# SPECCY2007.net
KiCad netlist of a schematic drawn in Altium Designer
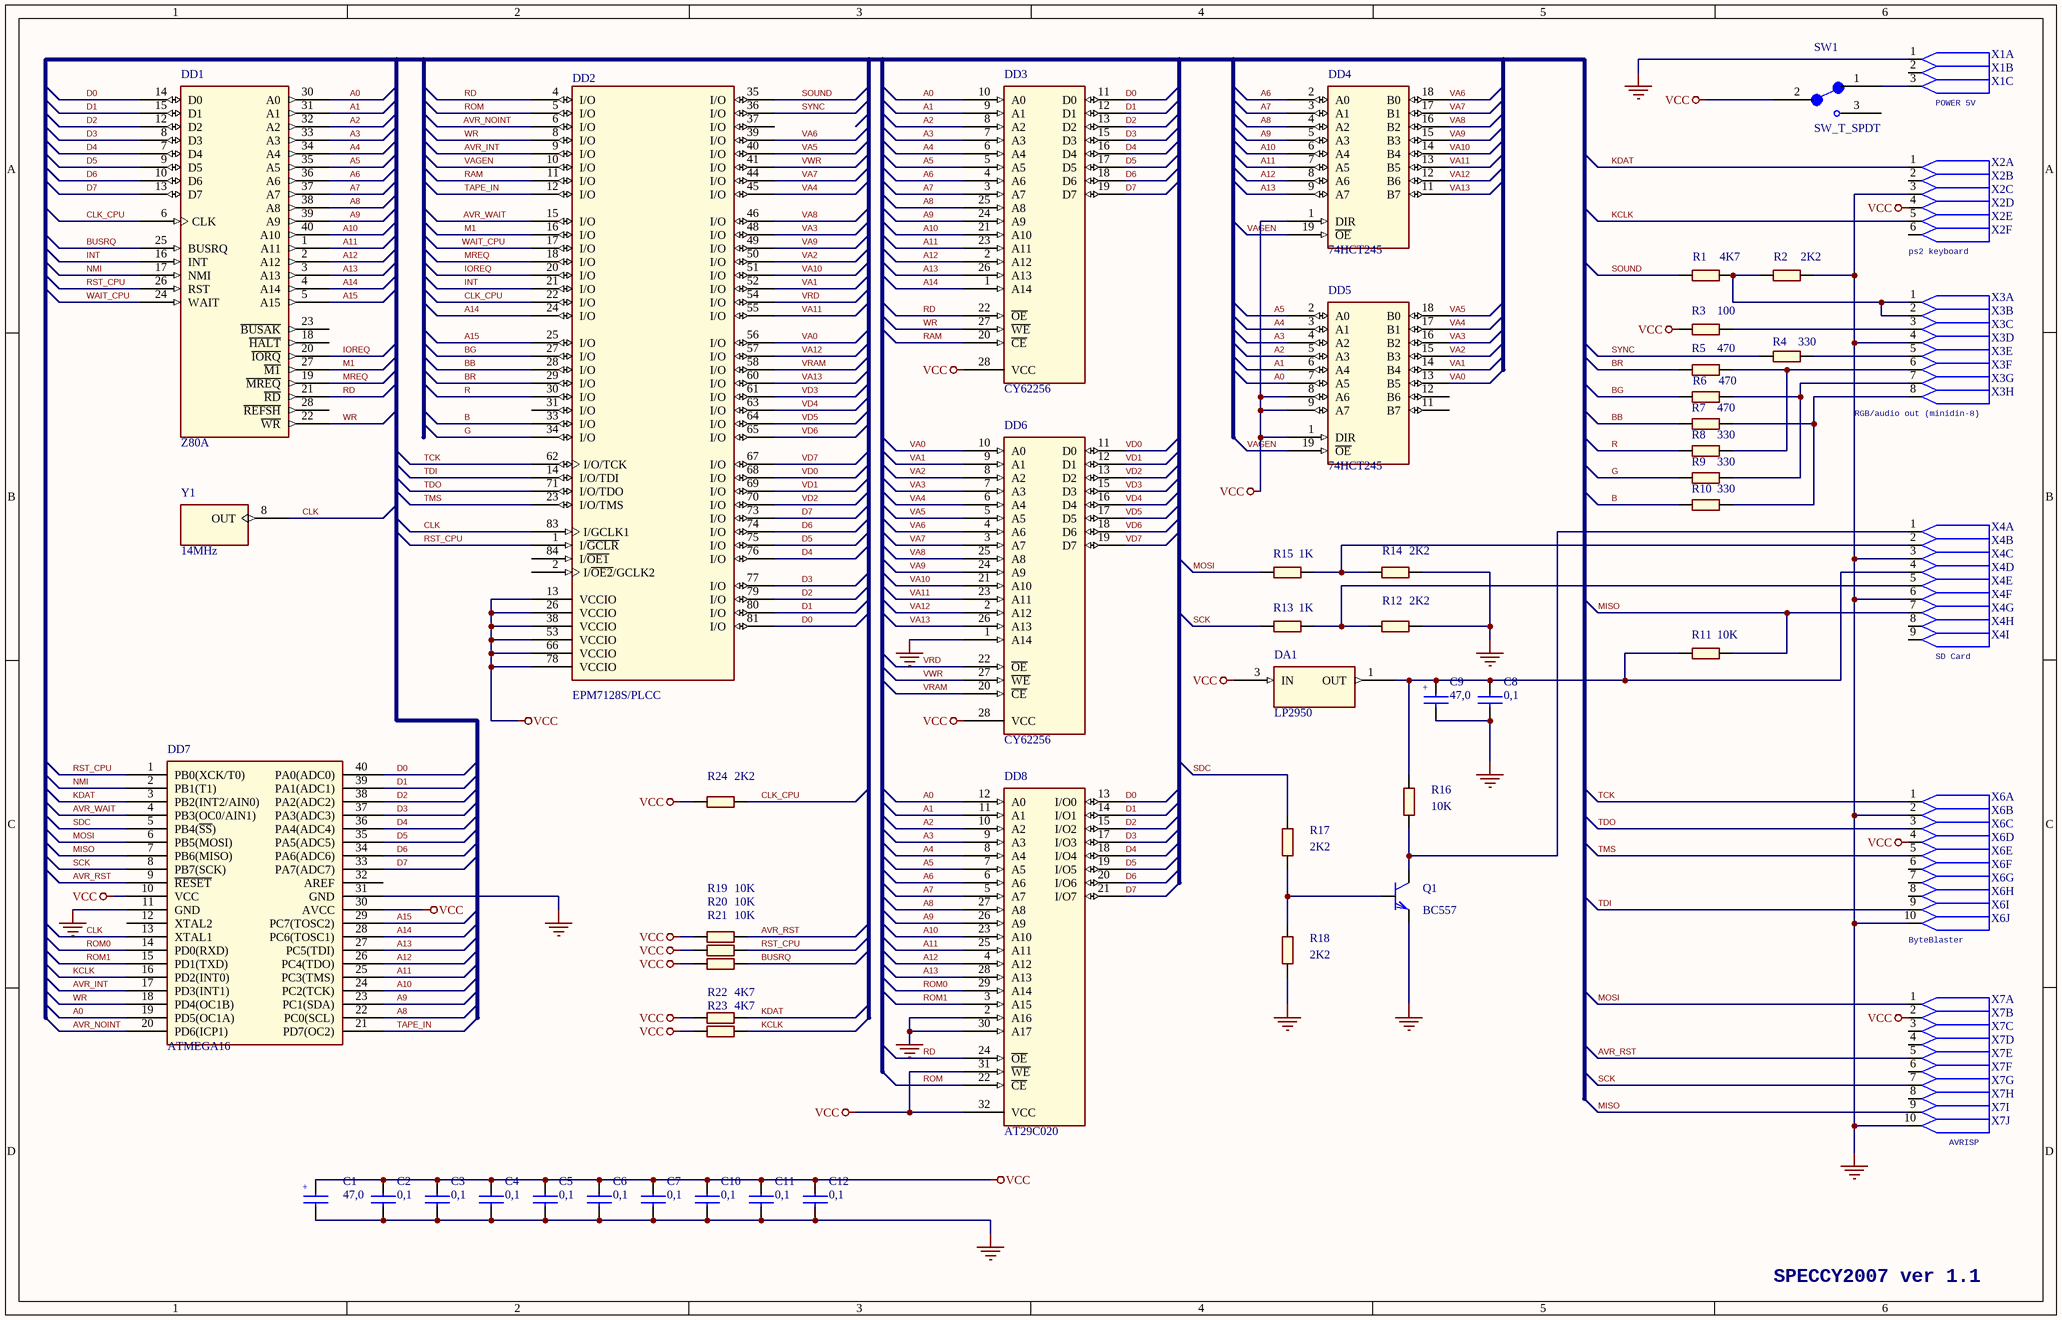
[diagram p0: SPECCY2007.SchDoc]

(export (version "E")
  (design (tool "Eeschema 10.0.6"))
  (components
    (comp (ref "C1")
      (value "47,0")
      (footprint "CAPPOL_2.54")
      (libsource (lib "SPECCY2007_Library") (part "C POL"))
    )
    (comp (ref "C2")
      (value "0,1")
      (footprint "CAP_5.08-7.8x3.2")
      (libsource (lib "SPECCY2007_Library") (part "C"))
    )
    (comp (ref "C3")
      (value "0,1")
      (footprint "CAP_5.08-7.8x3.2")
      (libsource (lib "SPECCY2007_Library") (part "C"))
    )
    (comp (ref "C4")
      (value "0,1")
      (footprint "CAP_5.08-7.8x3.2")
      (libsource (lib "SPECCY2007_Library") (part "C"))
    )
    (comp (ref "C5")
      (value "0,1")
      (footprint "CAP_5.08-7.8x3.2")
      (libsource (lib "SPECCY2007_Library") (part "C"))
    )
    (comp (ref "C6")
      (value "0,1")
      (footprint "CAP_5.08-7.8x3.2")
      (libsource (lib "SPECCY2007_Library") (part "C"))
    )
    (comp (ref "C7")
      (value "0,1")
      (footprint "CAP_5.08-7.8x3.2")
      (libsource (lib "SPECCY2007_Library") (part "C"))
    )
    (comp (ref "C8")
      (value "0,1")
      (footprint "CAP_5.08-7.8x3.2")
      (libsource (lib "SPECCY2007_Library") (part "C"))
    )
    (comp (ref "C9")
      (value "47,0")
      (footprint "CAPPOL_2.54")
      (libsource (lib "SPECCY2007_Library") (part "C POL"))
    )
    (comp (ref "C10")
      (value "0,1")
      (footprint "CAP_5.08-7.8x3.2")
      (libsource (lib "SPECCY2007_Library") (part "C"))
    )
    (comp (ref "C11")
      (value "0,1")
      (footprint "CAP_5.08-7.8x3.2")
      (libsource (lib "SPECCY2007_Library") (part "C"))
    )
    (comp (ref "C12")
      (value "0,1")
      (footprint "CAP_5.08-7.8x3.2")
      (libsource (lib "SPECCY2007_Library") (part "C"))
    )
    (comp (ref "DA1")
      (value "LP2950")
      (footprint "TO92")
      (libsource (lib "SPECCY2007_Library") (part "LP2950"))
    )
    (comp (ref "DD1")
      (value "Z80A")
      (footprint "DIP-40")
      (libsource (lib "SPECCY2007_Library") (part "Z80A"))
    )
    (comp (ref "DD2")
      (value "EPM7128S/PLCC")
      (footprint "PLCC84-Socket+AlteraMAX700S")
      (libsource (lib "SPECCY2007_Library") (part "EPM7128S/PLCC"))
    )
    (comp (ref "DD3")
      (value "CY62256")
      (footprint "DIP-28W")
      (libsource (lib "SPECCY2007_Library") (part "CY62256"))
    )
    (comp (ref "DD4")
      (value "74HCT245")
      (footprint "DIP-20")
      (libsource (lib "SPECCY2007_Library") (part "74HCT245"))
    )
    (comp (ref "DD5")
      (value "74HCT245")
      (footprint "DIP-20")
      (libsource (lib "SPECCY2007_Library") (part "74HCT245"))
    )
    (comp (ref "DD6")
      (value "CY62256")
      (footprint "DIP-28W")
      (libsource (lib "SPECCY2007_Library") (part "CY62256"))
    )
    (comp (ref "DD7")
      (value "ATMEGA16")
      (footprint "DIP-40")
      (libsource (lib "SPECCY2007_Library") (part "ATMEGA16"))
    )
    (comp (ref "DD8")
      (value "AT29C020")
      (footprint "DIP-32/D41.2")
      (libsource (lib "SPECCY2007_Library") (part "AT29C020"))
    )
    (comp (ref "Q1")
      (value "BC557")
      (footprint "TO92")
      (libsource (lib "SPECCY2007_Library") (part "TRANS NPN"))
    )
    (comp (ref "R1") (value "4K7") (footprint "RES_10.16") (libsource (lib "SPECCY2007_Library") (part "R")))
    (comp (ref "R2") (value "2K2") (footprint "RES_10.16") (libsource (lib "SPECCY2007_Library") (part "R")))
    (comp (ref "R3") (value "100") (footprint "RES_10.16") (libsource (lib "SPECCY2007_Library") (part "R")))
    (comp (ref "R4") (value "330") (footprint "RES_10.16") (libsource (lib "SPECCY2007_Library") (part "R")))
    (comp (ref "R5") (value "470") (footprint "RES_10.16") (libsource (lib "SPECCY2007_Library") (part "R")))
    (comp (ref "R6") (value "470") (footprint "RES_10.16") (libsource (lib "SPECCY2007_Library") (part "R")))
    (comp (ref "R7") (value "470") (footprint "RES_10.16") (libsource (lib "SPECCY2007_Library") (part "R")))
    (comp (ref "R8") (value "330") (footprint "RES_10.16") (libsource (lib "SPECCY2007_Library") (part "R")))
    (comp (ref "R9") (value "330") (footprint "RES_10.16") (libsource (lib "SPECCY2007_Library") (part "R")))
    (comp (ref "R10") (value "330") (footprint "RES_10.16") (libsource (lib "SPECCY2007_Library") (part "R")))
    (comp (ref "R11") (value "10K") (footprint "RES_10.16") (libsource (lib "SPECCY2007_Library") (part "R")))
    (comp (ref "R12") (value "2K2") (footprint "RES_10.16") (libsource (lib "SPECCY2007_Library") (part "R")))
    (comp (ref "R13") (value "1K") (footprint "RES_10.16") (libsource (lib "SPECCY2007_Library") (part "R")))
    (comp (ref "R14") (value "2K2") (footprint "RES_10.16") (libsource (lib "SPECCY2007_Library") (part "R")))
    (comp (ref "R15") (value "1K") (footprint "RES_10.16") (libsource (lib "SPECCY2007_Library") (part "R")))
    (comp (ref "R16") (value "10K") (footprint "RES_10.16") (libsource (lib "") (part "R_1")))
    (comp (ref "R17") (value "2K2") (footprint "RES_10.16") (libsource (lib "") (part "R_1")))
    (comp (ref "R18") (value "2K2") (footprint "RES_10.16") (libsource (lib "") (part "R_1")))
    (comp (ref "R19") (value "10K") (footprint "RES_10.16") (libsource (lib "SPECCY2007_Library") (part "R")))
    (comp (ref "R20") (value "10K") (footprint "RES_10.16") (libsource (lib "SPECCY2007_Library") (part "R")))
    (comp (ref "R21") (value "10K") (footprint "RES_10.16") (libsource (lib "SPECCY2007_Library") (part "R")))
    (comp (ref "R22") (value "4K7") (footprint "RES_10.16") (libsource (lib "SPECCY2007_Library") (part "R")))
    (comp (ref "R23") (value "4K7") (footprint "RES_10.16") (libsource (lib "SPECCY2007_Library") (part "R")))
    (comp (ref "R24") (value "2K2") (footprint "RES_10.16") (libsource (lib "SPECCY2007_Library") (part "R")))
    (comp (ref "SW1")
      (value "SW_T_SPDT")
      (footprint "SW_T_SPDT")
      (libsource (lib "SPECCY2007_Library") (part "SW_T_SPDT"))
    )
    (comp (ref "X1")
      (value "X3")
      (footprint "CONN JACK PWR")
      (libsource (lib "SPECCY2007_Library") (part "X3"))
    )
    (comp (ref "X2") (value "X6") (footprint "Mini-DIN6") (libsource (lib "SPECCY2007_Library") (part "X6")))
    (comp (ref "X3") (value "X8") (footprint "Mini-DIN8") (libsource (lib "SPECCY2007_Library") (part "X8")))
    (comp (ref "X4")
      (value "X9")
      (footprint "SD Card socket")
      (description "SD Card socket")
      (libsource (lib "SPECCY2007_Library") (part "X9"))
    )
    (comp (ref "X6")
      (value "X10")
      (footprint "Double row pin strip 5 way")
      (libsource (lib "SPECCY2007_Library") (part "X10"))
    )
    (comp (ref "X7")
      (value "X10")
      (footprint "Double row pin strip 5 way")
      (libsource (lib "SPECCY2007_Library") (part "X10"))
    )
    (comp (ref "Y1")
      (value "14MHz")
      (footprint "OSC14")
      (libsource (lib "SPECCY2007_Library") (part "OSC14"))
    )
  )
  (nets
    (net (code "1") (name "/A0") (class "Default")
      (node (ref "DD1") (pin "30") (pinfunction "A0_30") (pintype "output"))
      (node (ref "DD3") (pin "10") (pinfunction "A0_10") (pintype "input"))
      (node (ref "DD5") (pin "7") (pinfunction "A5_7") (pintype "bidirectional"))
      (node (ref "DD7") (pin "19") (pinfunction "PD5(OC1A)_19") (pintype "passive"))
      (node (ref "DD8") (pin "12") (pinfunction "A0_12") (pintype "input"))
    )
    (net (code "2") (name "/A1") (class "Default")
      (node (ref "DD1") (pin "31") (pinfunction "A1_31") (pintype "output"))
      (node (ref "DD3") (pin "9") (pinfunction "A1_9") (pintype "input"))
      (node (ref "DD5") (pin "6") (pinfunction "A4_6") (pintype "bidirectional"))
      (node (ref "DD8") (pin "11") (pinfunction "A1_11") (pintype "input"))
    )
    (net (code "3") (name "/A2") (class "Default")
      (node (ref "DD1") (pin "32") (pinfunction "A2_32") (pintype "output"))
      (node (ref "DD3") (pin "8") (pinfunction "A2_8") (pintype "input"))
      (node (ref "DD5") (pin "5") (pinfunction "A3_5") (pintype "bidirectional"))
      (node (ref "DD8") (pin "10") (pinfunction "A2_10") (pintype "input"))
    )
    (net (code "4") (name "/A3") (class "Default")
      (node (ref "DD1") (pin "33") (pinfunction "A3_33") (pintype "output"))
      (node (ref "DD3") (pin "7") (pinfunction "A3_7") (pintype "input"))
      (node (ref "DD5") (pin "4") (pinfunction "A2_4") (pintype "bidirectional"))
      (node (ref "DD8") (pin "9") (pinfunction "A3_9") (pintype "input"))
    )
    (net (code "5") (name "/A4") (class "Default")
      (node (ref "DD1") (pin "34") (pinfunction "A4_34") (pintype "output"))
      (node (ref "DD3") (pin "6") (pinfunction "A4_6") (pintype "input"))
      (node (ref "DD5") (pin "3") (pinfunction "A1_3") (pintype "bidirectional"))
      (node (ref "DD8") (pin "8") (pinfunction "A4_8") (pintype "input"))
    )
    (net (code "6") (name "/A5") (class "Default")
      (node (ref "DD1") (pin "35") (pinfunction "A5_35") (pintype "output"))
      (node (ref "DD3") (pin "5") (pinfunction "A5_5") (pintype "input"))
      (node (ref "DD5") (pin "2") (pinfunction "A0_2") (pintype "bidirectional"))
      (node (ref "DD8") (pin "7") (pinfunction "A5_7") (pintype "input"))
    )
    (net (code "7") (name "/A6") (class "Default")
      (node (ref "DD1") (pin "36") (pinfunction "A6_36") (pintype "output"))
      (node (ref "DD3") (pin "4") (pinfunction "A6_4") (pintype "input"))
      (node (ref "DD4") (pin "2") (pinfunction "A0_2") (pintype "bidirectional"))
      (node (ref "DD8") (pin "6") (pinfunction "A6_6") (pintype "input"))
    )
    (net (code "8") (name "/A7") (class "Default")
      (node (ref "DD1") (pin "37") (pinfunction "A7_37") (pintype "output"))
      (node (ref "DD3") (pin "3") (pinfunction "A7_3") (pintype "input"))
      (node (ref "DD4") (pin "3") (pinfunction "A1_3") (pintype "bidirectional"))
      (node (ref "DD8") (pin "5") (pinfunction "A7_5") (pintype "input"))
    )
    (net (code "9") (name "/A8") (class "Default")
      (node (ref "DD1") (pin "38") (pinfunction "A8_38") (pintype "output"))
      (node (ref "DD3") (pin "25") (pinfunction "A8_25") (pintype "input"))
      (node (ref "DD4") (pin "4") (pinfunction "A2_4") (pintype "bidirectional"))
      (node (ref "DD7") (pin "22") (pinfunction "PC0(SCL)_22") (pintype "passive"))
      (node (ref "DD8") (pin "27") (pinfunction "A8_27") (pintype "input"))
    )
    (net (code "10") (name "/A9") (class "Default")
      (node (ref "DD1") (pin "39") (pinfunction "A9_39") (pintype "output"))
      (node (ref "DD3") (pin "24") (pinfunction "A9_24") (pintype "input"))
      (node (ref "DD4") (pin "5") (pinfunction "A3_5") (pintype "bidirectional"))
      (node (ref "DD7") (pin "23") (pinfunction "PC1(SDA)_23") (pintype "passive"))
      (node (ref "DD8") (pin "26") (pinfunction "A9_26") (pintype "input"))
    )
    (net (code "11") (name "/A10") (class "Default")
      (node (ref "DD1") (pin "40") (pinfunction "A10_40") (pintype "output"))
      (node (ref "DD3") (pin "21") (pinfunction "A10_21") (pintype "input"))
      (node (ref "DD4") (pin "6") (pinfunction "A4_6") (pintype "bidirectional"))
      (node (ref "DD7") (pin "24") (pinfunction "PC2(TCK)_24") (pintype "passive"))
      (node (ref "DD8") (pin "23") (pinfunction "A10_23") (pintype "input"))
    )
    (net (code "12") (name "/A11") (class "Default")
      (node (ref "DD1") (pin "1") (pinfunction "A11_1") (pintype "output"))
      (node (ref "DD3") (pin "23") (pinfunction "A11_23") (pintype "input"))
      (node (ref "DD4") (pin "7") (pinfunction "A5_7") (pintype "bidirectional"))
      (node (ref "DD7") (pin "25") (pinfunction "PC3(TMS)_25") (pintype "passive"))
      (node (ref "DD8") (pin "25") (pinfunction "A11_25") (pintype "input"))
    )
    (net (code "13") (name "/A12") (class "Default")
      (node (ref "DD1") (pin "2") (pinfunction "A12_2") (pintype "output"))
      (node (ref "DD3") (pin "2") (pinfunction "A12_2") (pintype "input"))
      (node (ref "DD4") (pin "8") (pinfunction "A6_8") (pintype "bidirectional"))
      (node (ref "DD7") (pin "26") (pinfunction "PC4(TDO)_26") (pintype "passive"))
      (node (ref "DD8") (pin "4") (pinfunction "A12_4") (pintype "input"))
    )
    (net (code "14") (name "/A13") (class "Default")
      (node (ref "DD1") (pin "3") (pinfunction "A13_3") (pintype "output"))
      (node (ref "DD3") (pin "26") (pinfunction "A13_26") (pintype "input"))
      (node (ref "DD4") (pin "9") (pinfunction "A7_9") (pintype "bidirectional"))
      (node (ref "DD7") (pin "27") (pinfunction "PC5(TDI)_27") (pintype "passive"))
      (node (ref "DD8") (pin "28") (pinfunction "A13_28") (pintype "input"))
    )
    (net (code "15") (name "/A14") (class "Default")
      (node (ref "DD1") (pin "4") (pinfunction "A14_4") (pintype "output"))
      (node (ref "DD2") (pin "24") (pinfunction "I/O_24") (pintype "bidirectional"))
      (node (ref "DD3") (pin "1") (pinfunction "A14_1") (pintype "input"))
      (node (ref "DD7") (pin "28") (pinfunction "PC6(TOSC1)_28") (pintype "passive"))
    )
    (net (code "16") (name "/A15") (class "Default")
      (node (ref "DD1") (pin "5") (pinfunction "A15_5") (pintype "output"))
      (node (ref "DD2") (pin "25") (pinfunction "I/O_25") (pintype "bidirectional"))
      (node (ref "DD7") (pin "29") (pinfunction "PC7(TOSC2)_29") (pintype "passive"))
    )
    (net (code "17") (name "/AVR_INT") (class "Default")
      (node (ref "DD2") (pin "9") (pinfunction "I/O_9") (pintype "bidirectional"))
      (node (ref "DD7") (pin "17") (pinfunction "PD3(INT1)_17") (pintype "passive"))
    )
    (net (code "18") (name "/AVR_NOINT") (class "Default")
      (node (ref "DD2") (pin "6") (pinfunction "I/O_6") (pintype "bidirectional"))
      (node (ref "DD7") (pin "20") (pinfunction "PD6(ICP1)_20") (pintype "passive"))
    )
    (net (code "19") (name "/AVR_RST") (class "Default")
      (node (ref "DD7") (pin "9") (pinfunction "~{RESET}_9") (pintype "passive"))
      (node (ref "R19") (pin "2") (pinfunction "2_2") (pintype "passive"))
      (node (ref "X7") (pin "5") (pinfunction "CON_5") (pintype "passive"))
    )
    (net (code "20") (name "/AVR_WAIT") (class "Default")
      (node (ref "DD2") (pin "15") (pinfunction "I/O_15") (pintype "bidirectional"))
      (node (ref "DD7") (pin "4") (pinfunction "PB3(OC0/AIN1)_4") (pintype "passive"))
    )
    (net (code "21") (name "/B") (class "Default")
      (node (ref "DD2") (pin "33") (pinfunction "I/O_33") (pintype "bidirectional"))
      (node (ref "R10") (pin "1") (pinfunction "1_1") (pintype "passive"))
    )
    (net (code "22") (name "/BB") (class "Default")
      (node (ref "DD2") (pin "28") (pinfunction "I/O_28") (pintype "bidirectional"))
      (node (ref "R7") (pin "1") (pinfunction "1_1") (pintype "passive"))
    )
    (net (code "23") (name "/BG") (class "Default")
      (node (ref "DD2") (pin "27") (pinfunction "I/O_27") (pintype "bidirectional"))
      (node (ref "R6") (pin "1") (pinfunction "1_1") (pintype "passive"))
    )
    (net (code "24") (name "/BR") (class "Default")
      (node (ref "DD2") (pin "29") (pinfunction "I/O_29") (pintype "bidirectional"))
      (node (ref "R5") (pin "1") (pinfunction "1_1") (pintype "passive"))
    )
    (net (code "25") (name "/BUSRQ") (class "Default")
      (node (ref "DD1") (pin "25") (pinfunction "BUSRQ_25") (pintype "input"))
      (node (ref "R21") (pin "2") (pinfunction "2_2") (pintype "passive"))
    )
    (net (code "26") (name "/CLK") (class "Default")
      (node (ref "DD2") (pin "83") (pinfunction "I/GCLK1_83") (pintype "input"))
      (node (ref "DD7") (pin "13") (pinfunction "XTAL1_13") (pintype "passive"))
      (node (ref "Y1") (pin "8") (pinfunction "OUT_8") (pintype "output"))
    )
    (net (code "27") (name "/CLK_CPU") (class "Default")
      (node (ref "DD1") (pin "6") (pinfunction "CLK_6") (pintype "input"))
      (node (ref "DD2") (pin "22") (pinfunction "I/O_22") (pintype "bidirectional"))
      (node (ref "R24") (pin "2") (pinfunction "2_2") (pintype "passive"))
    )
    (net (code "28") (name "/D0") (class "Default")
      (node (ref "DD1") (pin "14") (pinfunction "D0_14") (pintype "bidirectional"))
      (node (ref "DD2") (pin "81") (pinfunction "I/O_81") (pintype "bidirectional"))
      (node (ref "DD3") (pin "11") (pinfunction "D0_11") (pintype "bidirectional"))
      (node (ref "DD7") (pin "40") (pinfunction "PA0(ADC0)_40") (pintype "passive"))
      (node (ref "DD8") (pin "13") (pinfunction "I/O0_13") (pintype "bidirectional"))
    )
    (net (code "29") (name "/D1") (class "Default")
      (node (ref "DD1") (pin "15") (pinfunction "D1_15") (pintype "bidirectional"))
      (node (ref "DD2") (pin "80") (pinfunction "I/O_80") (pintype "bidirectional"))
      (node (ref "DD3") (pin "12") (pinfunction "D1_12") (pintype "bidirectional"))
      (node (ref "DD7") (pin "39") (pinfunction "PA1(ADC1)_39") (pintype "passive"))
      (node (ref "DD8") (pin "14") (pinfunction "I/O1_14") (pintype "bidirectional"))
    )
    (net (code "30") (name "/D2") (class "Default")
      (node (ref "DD1") (pin "12") (pinfunction "D2_12") (pintype "bidirectional"))
      (node (ref "DD2") (pin "79") (pinfunction "I/O_79") (pintype "bidirectional"))
      (node (ref "DD3") (pin "13") (pinfunction "D2_13") (pintype "bidirectional"))
      (node (ref "DD7") (pin "38") (pinfunction "PA2(ADC2)_38") (pintype "passive"))
      (node (ref "DD8") (pin "15") (pinfunction "I/O2_15") (pintype "bidirectional"))
    )
    (net (code "31") (name "/D3") (class "Default")
      (node (ref "DD1") (pin "8") (pinfunction "D3_8") (pintype "bidirectional"))
      (node (ref "DD2") (pin "77") (pinfunction "I/O_77") (pintype "bidirectional"))
      (node (ref "DD3") (pin "15") (pinfunction "D3_15") (pintype "bidirectional"))
      (node (ref "DD7") (pin "37") (pinfunction "PA3(ADC3)_37") (pintype "passive"))
      (node (ref "DD8") (pin "17") (pinfunction "I/O3_17") (pintype "bidirectional"))
    )
    (net (code "32") (name "/D4") (class "Default")
      (node (ref "DD1") (pin "7") (pinfunction "D4_7") (pintype "bidirectional"))
      (node (ref "DD2") (pin "76") (pinfunction "I/O_76") (pintype "bidirectional"))
      (node (ref "DD3") (pin "16") (pinfunction "D4_16") (pintype "bidirectional"))
      (node (ref "DD7") (pin "36") (pinfunction "PA4(ADC4)_36") (pintype "passive"))
      (node (ref "DD8") (pin "18") (pinfunction "I/O4_18") (pintype "bidirectional"))
    )
    (net (code "33") (name "/D5") (class "Default")
      (node (ref "DD1") (pin "9") (pinfunction "D5_9") (pintype "bidirectional"))
      (node (ref "DD2") (pin "75") (pinfunction "I/O_75") (pintype "bidirectional"))
      (node (ref "DD3") (pin "17") (pinfunction "D5_17") (pintype "bidirectional"))
      (node (ref "DD7") (pin "35") (pinfunction "PA5(ADC5)_35") (pintype "passive"))
      (node (ref "DD8") (pin "19") (pinfunction "I/O5_19") (pintype "bidirectional"))
    )
    (net (code "34") (name "/D6") (class "Default")
      (node (ref "DD1") (pin "10") (pinfunction "D6_10") (pintype "bidirectional"))
      (node (ref "DD2") (pin "74") (pinfunction "I/O_74") (pintype "bidirectional"))
      (node (ref "DD3") (pin "18") (pinfunction "D6_18") (pintype "bidirectional"))
      (node (ref "DD7") (pin "34") (pinfunction "PA6(ADC6)_34") (pintype "passive"))
      (node (ref "DD8") (pin "20") (pinfunction "I/O6_20") (pintype "bidirectional"))
    )
    (net (code "35") (name "/D7") (class "Default")
      (node (ref "DD1") (pin "13") (pinfunction "D7_13") (pintype "bidirectional"))
      (node (ref "DD2") (pin "73") (pinfunction "I/O_73") (pintype "bidirectional"))
      (node (ref "DD3") (pin "19") (pinfunction "D7_19") (pintype "bidirectional"))
      (node (ref "DD7") (pin "33") (pinfunction "PA7(ADC7)_33") (pintype "passive"))
      (node (ref "DD8") (pin "21") (pinfunction "I/O7_21") (pintype "bidirectional"))
    )
    (net (code "36") (name "/G") (class "Default")
      (node (ref "DD2") (pin "34") (pinfunction "I/O_34") (pintype "bidirectional"))
      (node (ref "R9") (pin "1") (pinfunction "1_1") (pintype "passive"))
    )
    (net (code "37") (name "/INT") (class "Default")
      (node (ref "DD1") (pin "16") (pinfunction "INT_16") (pintype "input"))
      (node (ref "DD2") (pin "21") (pinfunction "I/O_21") (pintype "bidirectional"))
    )
    (net (code "38") (name "/IOREQ") (class "Default")
      (node (ref "DD1") (pin "20") (pinfunction "~{IORQ}_20") (pintype "output"))
      (node (ref "DD2") (pin "20") (pinfunction "I/O_20") (pintype "bidirectional"))
    )
    (net (code "39") (name "/KCLK") (class "Default")
      (node (ref "DD7") (pin "16") (pinfunction "PD2(INT0)_16") (pintype "passive"))
      (node (ref "R23") (pin "2") (pinfunction "2_2") (pintype "passive"))
      (node (ref "X2") (pin "5") (pinfunction "CON_5") (pintype "passive"))
    )
    (net (code "40") (name "/KDAT") (class "Default")
      (node (ref "DD7") (pin "3") (pinfunction "PB2(INT2/AIN0)_3") (pintype "passive"))
      (node (ref "R22") (pin "2") (pinfunction "2_2") (pintype "passive"))
      (node (ref "X2") (pin "1") (pinfunction "CON_1") (pintype "passive"))
    )
    (net (code "41") (name "/M1") (class "Default")
      (node (ref "DD1") (pin "27") (pinfunction "~{M1}_27") (pintype "output"))
      (node (ref "DD2") (pin "16") (pinfunction "I/O_16") (pintype "bidirectional"))
    )
    (net (code "42") (name "/MISO") (class "Default")
      (node (ref "DD7") (pin "7") (pinfunction "PB6(MISO)_7") (pintype "passive"))
      (node (ref "R11") (pin "2") (pinfunction "2_2") (pintype "passive"))
      (node (ref "X4") (pin "7") (pinfunction "CON_7") (pintype "passive"))
      (node (ref "X7") (pin "9") (pinfunction "CON_9") (pintype "passive"))
    )
    (net (code "43") (name "/MOSI") (class "Default")
      (node (ref "DD7") (pin "6") (pinfunction "PB5(MOSI)_6") (pintype "passive"))
      (node (ref "R15") (pin "1") (pinfunction "1_1") (pintype "passive"))
      (node (ref "X7") (pin "1") (pinfunction "CON_1") (pintype "passive"))
    )
    (net (code "44") (name "/MREQ") (class "Default")
      (node (ref "DD1") (pin "19") (pinfunction "~{MREQ}_19") (pintype "output"))
      (node (ref "DD2") (pin "18") (pinfunction "I/O_18") (pintype "bidirectional"))
    )
    (net (code "45") (name "/NMI") (class "Default")
      (node (ref "DD1") (pin "17") (pinfunction "NMI_17") (pintype "input"))
      (node (ref "DD7") (pin "2") (pinfunction "PB1(T1)_2") (pintype "passive"))
    )
    (net (code "46") (name "/R") (class "Default")
      (node (ref "DD2") (pin "30") (pinfunction "I/O_30") (pintype "bidirectional"))
      (node (ref "R8") (pin "1") (pinfunction "1_1") (pintype "passive"))
    )
    (net (code "47") (name "/RAM") (class "Default")
      (node (ref "DD2") (pin "11") (pinfunction "I/O_11") (pintype "bidirectional"))
      (node (ref "DD3") (pin "20") (pinfunction "~{CE}_20") (pintype "input"))
    )
    (net (code "48") (name "/RD") (class "Default")
      (node (ref "DD1") (pin "21") (pinfunction "~{RD}_21") (pintype "output"))
      (node (ref "DD2") (pin "4") (pinfunction "I/O_4") (pintype "bidirectional"))
      (node (ref "DD3") (pin "22") (pinfunction "~{OE}_22") (pintype "input"))
      (node (ref "DD8") (pin "24") (pinfunction "~{OE}_24") (pintype "input"))
    )
    (net (code "49") (name "/ROM") (class "Default")
      (node (ref "DD2") (pin "5") (pinfunction "I/O_5") (pintype "bidirectional"))
      (node (ref "DD8") (pin "22") (pinfunction "~{CE}_22") (pintype "input"))
    )
    (net (code "50") (name "/ROM0") (class "Default")
      (node (ref "DD7") (pin "14") (pinfunction "PD0(RXD)_14") (pintype "passive"))
      (node (ref "DD8") (pin "29") (pinfunction "A14_29") (pintype "input"))
    )
    (net (code "51") (name "/ROM1") (class "Default")
      (node (ref "DD7") (pin "15") (pinfunction "PD1(TXD)_15") (pintype "passive"))
      (node (ref "DD8") (pin "3") (pinfunction "A15_3") (pintype "input"))
    )
    (net (code "52") (name "/RST_CPU") (class "Default")
      (node (ref "DD1") (pin "26") (pinfunction "RST_26") (pintype "input"))
      (node (ref "DD2") (pin "1") (pinfunction "I/~{GCLR}_1") (pintype "input"))
      (node (ref "DD7") (pin "1") (pinfunction "PB0(XCK/T0)_1") (pintype "passive"))
      (node (ref "R20") (pin "2") (pinfunction "2_2") (pintype "passive"))
    )
    (net (code "53") (name "/SCK") (class "Default")
      (node (ref "DD7") (pin "8") (pinfunction "PB7(SCK)_8") (pintype "passive"))
      (node (ref "R13") (pin "1") (pinfunction "1_1") (pintype "passive"))
      (node (ref "X7") (pin "7") (pinfunction "CON_7") (pintype "passive"))
    )
    (net (code "54") (name "/SDC") (class "Default")
      (node (ref "DD7") (pin "5") (pinfunction "PB4(~{SS})_5") (pintype "passive"))
      (node (ref "R17") (pin "2") (pinfunction "2_2") (pintype "passive"))
    )
    (net (code "55") (name "/SOUND") (class "Default")
      (node (ref "DD2") (pin "35") (pinfunction "I/O_35") (pintype "bidirectional"))
      (node (ref "R1") (pin "1") (pinfunction "1_1") (pintype "passive"))
    )
    (net (code "56") (name "/SYNC") (class "Default")
      (node (ref "DD2") (pin "36") (pinfunction "I/O_36") (pintype "bidirectional"))
      (node (ref "R4") (pin "1") (pinfunction "1_1") (pintype "passive"))
    )
    (net (code "57") (name "/TAPE_IN") (class "Default")
      (node (ref "DD2") (pin "12") (pinfunction "I/O_12") (pintype "bidirectional"))
      (node (ref "DD7") (pin "21") (pinfunction "PD7(OC2)_21") (pintype "passive"))
    )
    (net (code "58") (name "/TCK") (class "Default")
      (node (ref "DD2") (pin "62") (pinfunction "I/O/TCK_62") (pintype "bidirectional"))
      (node (ref "X6") (pin "1") (pinfunction "CON_1") (pintype "passive"))
    )
    (net (code "59") (name "/TDI") (class "Default")
      (node (ref "DD2") (pin "14") (pinfunction "I/O/TDI_14") (pintype "bidirectional"))
      (node (ref "X6") (pin "9") (pinfunction "CON_9") (pintype "passive"))
    )
    (net (code "60") (name "/TDO") (class "Default")
      (node (ref "DD2") (pin "71") (pinfunction "I/O/TDO_71") (pintype "bidirectional"))
      (node (ref "X6") (pin "3") (pinfunction "CON_3") (pintype "passive"))
    )
    (net (code "61") (name "/TMS") (class "Default")
      (node (ref "DD2") (pin "23") (pinfunction "I/O/TMS_23") (pintype "bidirectional"))
      (node (ref "X6") (pin "5") (pinfunction "CON_5") (pintype "passive"))
    )
    (net (code "62") (name "/VA0") (class "Default")
      (node (ref "DD2") (pin "56") (pinfunction "I/O_56") (pintype "bidirectional"))
      (node (ref "DD5") (pin "13") (pinfunction "B5_13") (pintype "bidirectional"))
      (node (ref "DD6") (pin "10") (pinfunction "A0_10") (pintype "input"))
    )
    (net (code "63") (name "/VA1") (class "Default")
      (node (ref "DD2") (pin "52") (pinfunction "I/O_52") (pintype "bidirectional"))
      (node (ref "DD5") (pin "14") (pinfunction "B4_14") (pintype "bidirectional"))
      (node (ref "DD6") (pin "9") (pinfunction "A1_9") (pintype "input"))
    )
    (net (code "64") (name "/VA2") (class "Default")
      (node (ref "DD2") (pin "50") (pinfunction "I/O_50") (pintype "bidirectional"))
      (node (ref "DD5") (pin "15") (pinfunction "B3_15") (pintype "bidirectional"))
      (node (ref "DD6") (pin "8") (pinfunction "A2_8") (pintype "input"))
    )
    (net (code "65") (name "/VA3") (class "Default")
      (node (ref "DD2") (pin "48") (pinfunction "I/O_48") (pintype "bidirectional"))
      (node (ref "DD5") (pin "16") (pinfunction "B2_16") (pintype "bidirectional"))
      (node (ref "DD6") (pin "7") (pinfunction "A3_7") (pintype "input"))
    )
    (net (code "66") (name "/VA4") (class "Default")
      (node (ref "DD2") (pin "45") (pinfunction "I/O_45") (pintype "bidirectional"))
      (node (ref "DD5") (pin "17") (pinfunction "B1_17") (pintype "bidirectional"))
      (node (ref "DD6") (pin "6") (pinfunction "A4_6") (pintype "input"))
    )
    (net (code "67") (name "/VA5") (class "Default")
      (node (ref "DD2") (pin "40") (pinfunction "I/O_40") (pintype "bidirectional"))
      (node (ref "DD5") (pin "18") (pinfunction "B0_18") (pintype "bidirectional"))
      (node (ref "DD6") (pin "5") (pinfunction "A5_5") (pintype "input"))
    )
    (net (code "68") (name "/VA6") (class "Default")
      (node (ref "DD2") (pin "39") (pinfunction "I/O_39") (pintype "bidirectional"))
      (node (ref "DD4") (pin "18") (pinfunction "B0_18") (pintype "bidirectional"))
      (node (ref "DD6") (pin "4") (pinfunction "A6_4") (pintype "input"))
    )
    (net (code "69") (name "/VA7") (class "Default")
      (node (ref "DD2") (pin "44") (pinfunction "I/O_44") (pintype "bidirectional"))
      (node (ref "DD4") (pin "17") (pinfunction "B1_17") (pintype "bidirectional"))
      (node (ref "DD6") (pin "3") (pinfunction "A7_3") (pintype "input"))
    )
    (net (code "70") (name "/VA8") (class "Default")
      (node (ref "DD2") (pin "46") (pinfunction "I/O_46") (pintype "bidirectional"))
      (node (ref "DD4") (pin "16") (pinfunction "B2_16") (pintype "bidirectional"))
      (node (ref "DD6") (pin "25") (pinfunction "A8_25") (pintype "input"))
    )
    (net (code "71") (name "/VA9") (class "Default")
      (node (ref "DD2") (pin "49") (pinfunction "I/O_49") (pintype "bidirectional"))
      (node (ref "DD4") (pin "15") (pinfunction "B3_15") (pintype "bidirectional"))
      (node (ref "DD6") (pin "24") (pinfunction "A9_24") (pintype "input"))
    )
    (net (code "72") (name "/VA10") (class "Default")
      (node (ref "DD2") (pin "51") (pinfunction "I/O_51") (pintype "bidirectional"))
      (node (ref "DD4") (pin "14") (pinfunction "B4_14") (pintype "bidirectional"))
      (node (ref "DD6") (pin "21") (pinfunction "A10_21") (pintype "input"))
    )
    (net (code "73") (name "/VA11") (class "Default")
      (node (ref "DD2") (pin "55") (pinfunction "I/O_55") (pintype "bidirectional"))
      (node (ref "DD4") (pin "13") (pinfunction "B5_13") (pintype "bidirectional"))
      (node (ref "DD6") (pin "23") (pinfunction "A11_23") (pintype "input"))
    )
    (net (code "74") (name "/VA12") (class "Default")
      (node (ref "DD2") (pin "57") (pinfunction "I/O_57") (pintype "bidirectional"))
      (node (ref "DD4") (pin "12") (pinfunction "B6_12") (pintype "bidirectional"))
      (node (ref "DD6") (pin "2") (pinfunction "A12_2") (pintype "input"))
    )
    (net (code "75") (name "/VA13") (class "Default")
      (node (ref "DD2") (pin "60") (pinfunction "I/O_60") (pintype "bidirectional"))
      (node (ref "DD4") (pin "11") (pinfunction "B7_11") (pintype "bidirectional"))
      (node (ref "DD6") (pin "26") (pinfunction "A13_26") (pintype "input"))
    )
    (net (code "76") (name "/VAGEN") (class "Default")
      (node (ref "DD2") (pin "10") (pinfunction "I/O_10") (pintype "bidirectional"))
      (node (ref "DD4") (pin "19") (pinfunction "~{OE}_19") (pintype "input"))
      (node (ref "DD5") (pin "19") (pinfunction "~{OE}_19") (pintype "input"))
    )
    (net (code "77") (name "/VD0") (class "Default")
      (node (ref "DD2") (pin "68") (pinfunction "I/O_68") (pintype "bidirectional"))
      (node (ref "DD6") (pin "11") (pinfunction "D0_11") (pintype "bidirectional"))
    )
    (net (code "78") (name "/VD1") (class "Default")
      (node (ref "DD2") (pin "69") (pinfunction "I/O_69") (pintype "bidirectional"))
      (node (ref "DD6") (pin "12") (pinfunction "D1_12") (pintype "bidirectional"))
    )
    (net (code "79") (name "/VD2") (class "Default")
      (node (ref "DD2") (pin "70") (pinfunction "I/O_70") (pintype "bidirectional"))
      (node (ref "DD6") (pin "13") (pinfunction "D2_13") (pintype "bidirectional"))
    )
    (net (code "80") (name "/VD3") (class "Default")
      (node (ref "DD2") (pin "61") (pinfunction "I/O_61") (pintype "bidirectional"))
      (node (ref "DD6") (pin "15") (pinfunction "D3_15") (pintype "bidirectional"))
    )
    (net (code "81") (name "/VD4") (class "Default")
      (node (ref "DD2") (pin "63") (pinfunction "I/O_63") (pintype "bidirectional"))
      (node (ref "DD6") (pin "16") (pinfunction "D4_16") (pintype "bidirectional"))
    )
    (net (code "82") (name "/VD5") (class "Default")
      (node (ref "DD2") (pin "64") (pinfunction "I/O_64") (pintype "bidirectional"))
      (node (ref "DD6") (pin "17") (pinfunction "D5_17") (pintype "bidirectional"))
    )
    (net (code "83") (name "/VD6") (class "Default")
      (node (ref "DD2") (pin "65") (pinfunction "I/O_65") (pintype "bidirectional"))
      (node (ref "DD6") (pin "18") (pinfunction "D6_18") (pintype "bidirectional"))
    )
    (net (code "84") (name "/VD7") (class "Default")
      (node (ref "DD2") (pin "67") (pinfunction "I/O_67") (pintype "bidirectional"))
      (node (ref "DD6") (pin "19") (pinfunction "D7_19") (pintype "bidirectional"))
    )
    (net (code "85") (name "/VRAM") (class "Default")
      (node (ref "DD2") (pin "58") (pinfunction "I/O_58") (pintype "bidirectional"))
      (node (ref "DD6") (pin "20") (pinfunction "~{CE}_20") (pintype "input"))
    )
    (net (code "86") (name "/VRD") (class "Default")
      (node (ref "DD2") (pin "54") (pinfunction "I/O_54") (pintype "bidirectional"))
      (node (ref "DD6") (pin "22") (pinfunction "~{OE}_22") (pintype "input"))
    )
    (net (code "87") (name "/VWR") (class "Default")
      (node (ref "DD2") (pin "41") (pinfunction "I/O_41") (pintype "bidirectional"))
      (node (ref "DD6") (pin "27") (pinfunction "~{WE}_27") (pintype "input"))
    )
    (net (code "88") (name "/WAIT_CPU") (class "Default")
      (node (ref "DD1") (pin "24") (pinfunction "WAIT_24") (pintype "input"))
      (node (ref "DD2") (pin "17") (pinfunction "I/O_17") (pintype "bidirectional"))
    )
    (net (code "89") (name "/WR") (class "Default")
      (node (ref "DD1") (pin "22") (pinfunction "~{WR}_22") (pintype "output"))
      (node (ref "DD2") (pin "8") (pinfunction "I/O_8") (pintype "bidirectional"))
      (node (ref "DD3") (pin "27") (pinfunction "~{WE}_27") (pintype "input"))
      (node (ref "DD7") (pin "18") (pinfunction "PD4(OC1B)_18") (pintype "passive"))
    )
    (net (code "90") (name "GND") (class "Default")
      (node (ref "C1") (pin "MINUS") (pinfunction "MINUS_MINUS") (pintype "passive"))
      (node (ref "C10") (pin "2") (pinfunction "2_2") (pintype "passive"))
      (node (ref "C11") (pin "2") (pinfunction "2_2") (pintype "passive"))
      (node (ref "C12") (pin "2") (pinfunction "2_2") (pintype "passive"))
      (node (ref "C2") (pin "2") (pinfunction "2_2") (pintype "passive"))
      (node (ref "C3") (pin "2") (pinfunction "2_2") (pintype "passive"))
      (node (ref "C4") (pin "2") (pinfunction "2_2") (pintype "passive"))
      (node (ref "C5") (pin "2") (pinfunction "2_2") (pintype "passive"))
      (node (ref "C6") (pin "2") (pinfunction "2_2") (pintype "passive"))
      (node (ref "C7") (pin "2") (pinfunction "2_2") (pintype "passive"))
      (node (ref "C8") (pin "2") (pinfunction "2_2") (pintype "passive"))
      (node (ref "C9") (pin "MINUS") (pinfunction "MINUS_MINUS") (pintype "passive"))
      (node (ref "DA1") (pin "2") (pinfunction "GND_2") (pintype "power_in"))
      (node (ref "DD1") (pin "29") (pinfunction "GND_29") (pintype "power_in"))
      (node (ref "DD2") (pin "19") (pinfunction "GND_19") (pintype "power_in"))
      (node (ref "DD2") (pin "32") (pinfunction "GND_32") (pintype "power_in"))
      (node (ref "DD2") (pin "42") (pinfunction "GND_42") (pintype "power_in"))
      (node (ref "DD2") (pin "47") (pinfunction "GND_47") (pintype "power_in"))
      (node (ref "DD2") (pin "59") (pinfunction "GND_59") (pintype "power_in"))
      (node (ref "DD2") (pin "7") (pinfunction "GND_7") (pintype "power_in"))
      (node (ref "DD2") (pin "72") (pinfunction "GND_72") (pintype "power_in"))
      (node (ref "DD2") (pin "82") (pinfunction "GND_82") (pintype "power_in"))
      (node (ref "DD3") (pin "14") (pinfunction "GND_14") (pintype "power_in"))
      (node (ref "DD4") (pin "10") (pinfunction "GND_10") (pintype "power_in"))
      (node (ref "DD5") (pin "10") (pinfunction "GND_10") (pintype "power_in"))
      (node (ref "DD6") (pin "1") (pinfunction "A14_1") (pintype "input"))
      (node (ref "DD6") (pin "14") (pinfunction "GND_14") (pintype "power_in"))
      (node (ref "DD7") (pin "11") (pinfunction "GND_11") (pintype "passive"))
      (node (ref "DD7") (pin "31") (pinfunction "GND_31") (pintype "passive"))
      (node (ref "DD8") (pin "16") (pinfunction "GND_16") (pintype "power_in"))
      (node (ref "DD8") (pin "2") (pinfunction "A16_2") (pintype "input"))
      (node (ref "DD8") (pin "30") (pinfunction "A17_30") (pintype "input"))
      (node (ref "Q1") (pin "1") (pinfunction "e_1") (pintype "passive"))
      (node (ref "R12") (pin "2") (pinfunction "2_2") (pintype "passive"))
      (node (ref "R14") (pin "2") (pinfunction "2_2") (pintype "passive"))
      (node (ref "R18") (pin "1") (pinfunction "1_1") (pintype "passive"))
      (node (ref "R2") (pin "2") (pinfunction "2_2") (pintype "passive"))
      (node (ref "X1") (pin "1") (pinfunction "CON_1") (pintype "passive"))
      (node (ref "X2") (pin "3") (pinfunction "CON_3") (pintype "passive"))
      (node (ref "X3") (pin "4") (pinfunction "CON_4") (pintype "passive"))
      (node (ref "X4") (pin "3") (pinfunction "CON_3") (pintype "passive"))
      (node (ref "X4") (pin "6") (pinfunction "CON_6") (pintype "passive"))
      (node (ref "X6") (pin "10") (pinfunction "CON_10") (pintype "passive"))
      (node (ref "X6") (pin "2") (pinfunction "CON_2") (pintype "passive"))
      (node (ref "X7") (pin "10") (pinfunction "CON_10") (pintype "passive"))
      (node (ref "Y1") (pin "7") (pinfunction "GND_7") (pintype "power_in"))
    )
    (net (code "91") (name "Net-(DA1-OUT)") (class "Default")
      (node (ref "C8") (pin "1") (pinfunction "1_1") (pintype "passive"))
      (node (ref "C9") (pin "PLUS") (pinfunction "PLUS_PLUS") (pintype "passive"))
      (node (ref "DA1") (pin "1") (pinfunction "OUT_1") (pintype "output"))
      (node (ref "R11") (pin "1") (pinfunction "1_1") (pintype "passive"))
      (node (ref "R16") (pin "2") (pinfunction "2_2") (pintype "passive"))
      (node (ref "X4") (pin "4") (pinfunction "CON_4") (pintype "passive"))
    )
    (net (code "92") (name "Net-(Q1-b)") (class "Default")
      (node (ref "Q1") (pin "2") (pinfunction "b_2") (pintype "passive"))
      (node (ref "R17") (pin "1") (pinfunction "1_1") (pintype "passive"))
      (node (ref "R18") (pin "2") (pinfunction "2_2") (pintype "passive"))
    )
    (net (code "93") (name "Net-(Q1-c)") (class "Default")
      (node (ref "Q1") (pin "3") (pinfunction "c_3") (pintype "passive"))
      (node (ref "R16") (pin "1") (pinfunction "1_1") (pintype "passive"))
      (node (ref "X4") (pin "1") (pinfunction "CON_1") (pintype "passive"))
    )
    (net (code "94") (name "Net-(SW1-NC)") (class "Default")
      (node (ref "SW1") (pin "1") (pinfunction "NC_1") (pintype "passive"))
      (node (ref "X1") (pin "3") (pinfunction "CON_3") (pintype "passive"))
    )
    (net (code "95") (name "Net-(X3A-CON)") (class "Default")
      (node (ref "R1") (pin "2") (pinfunction "2_2") (pintype "passive"))
      (node (ref "R2") (pin "1") (pinfunction "1_1") (pintype "passive"))
      (node (ref "X3") (pin "1") (pinfunction "CON_1") (pintype "passive"))
      (node (ref "X3") (pin "2") (pinfunction "CON_2") (pintype "passive"))
    )
    (net (code "96") (name "Net-(X3C-CON)") (class "Default")
      (node (ref "R3") (pin "2") (pinfunction "2_2") (pintype "passive"))
      (node (ref "X3") (pin "3") (pinfunction "CON_3") (pintype "passive"))
    )
    (net (code "97") (name "Net-(X3E-CON)") (class "Default")
      (node (ref "R4") (pin "2") (pinfunction "2_2") (pintype "passive"))
      (node (ref "X3") (pin "5") (pinfunction "CON_5") (pintype "passive"))
    )
    (net (code "98") (name "Net-(X3F-CON)") (class "Default")
      (node (ref "R5") (pin "2") (pinfunction "2_2") (pintype "passive"))
      (node (ref "R8") (pin "2") (pinfunction "2_2") (pintype "passive"))
      (node (ref "X3") (pin "6") (pinfunction "CON_6") (pintype "passive"))
    )
    (net (code "99") (name "Net-(X3G-CON)") (class "Default")
      (node (ref "R6") (pin "2") (pinfunction "2_2") (pintype "passive"))
      (node (ref "R9") (pin "2") (pinfunction "2_2") (pintype "passive"))
      (node (ref "X3") (pin "7") (pinfunction "CON_7") (pintype "passive"))
    )
    (net (code "100") (name "Net-(X3H-CON)") (class "Default")
      (node (ref "R10") (pin "2") (pinfunction "2_2") (pintype "passive"))
      (node (ref "R7") (pin "2") (pinfunction "2_2") (pintype "passive"))
      (node (ref "X3") (pin "8") (pinfunction "CON_8") (pintype "passive"))
    )
    (net (code "101") (name "Net-(X4B-CON)") (class "Default")
      (node (ref "R14") (pin "1") (pinfunction "1_1") (pintype "passive"))
      (node (ref "R15") (pin "2") (pinfunction "2_2") (pintype "passive"))
      (node (ref "X4") (pin "2") (pinfunction "CON_2") (pintype "passive"))
    )
    (net (code "102") (name "Net-(X4E-CON)") (class "Default")
      (node (ref "R12") (pin "1") (pinfunction "1_1") (pintype "passive"))
      (node (ref "R13") (pin "2") (pinfunction "2_2") (pintype "passive"))
      (node (ref "X4") (pin "5") (pinfunction "CON_5") (pintype "passive"))
    )
    (net (code "103") (name "VCC") (class "Default")
      (node (ref "C1") (pin "PLUS") (pinfunction "PLUS_PLUS") (pintype "passive"))
      (node (ref "C10") (pin "1") (pinfunction "1_1") (pintype "passive"))
      (node (ref "C11") (pin "1") (pinfunction "1_1") (pintype "passive"))
      (node (ref "C12") (pin "1") (pinfunction "1_1") (pintype "passive"))
      (node (ref "C2") (pin "1") (pinfunction "1_1") (pintype "passive"))
      (node (ref "C3") (pin "1") (pinfunction "1_1") (pintype "passive"))
      (node (ref "C4") (pin "1") (pinfunction "1_1") (pintype "passive"))
      (node (ref "C5") (pin "1") (pinfunction "1_1") (pintype "passive"))
      (node (ref "C6") (pin "1") (pinfunction "1_1") (pintype "passive"))
      (node (ref "C7") (pin "1") (pinfunction "1_1") (pintype "passive"))
      (node (ref "DA1") (pin "3") (pinfunction "IN_3") (pintype "input"))
      (node (ref "DD1") (pin "11") (pinfunction "VCC_11") (pintype "power_in"))
      (node (ref "DD2") (pin "13") (pinfunction "VCCIO_13") (pintype "power_in"))
      (node (ref "DD2") (pin "26") (pinfunction "VCCIO_26") (pintype "power_in"))
      (node (ref "DD2") (pin "3") (pinfunction "VCC_3") (pintype "power_in"))
      (node (ref "DD2") (pin "38") (pinfunction "VCCIO_38") (pintype "power_in"))
      (node (ref "DD2") (pin "43") (pinfunction "VCC_43") (pintype "power_in"))
      (node (ref "DD2") (pin "53") (pinfunction "VCCIO_53") (pintype "power_in"))
      (node (ref "DD2") (pin "66") (pinfunction "VCCIO_66") (pintype "power_in"))
      (node (ref "DD2") (pin "78") (pinfunction "VCCIO_78") (pintype "power_in"))
      (node (ref "DD3") (pin "28") (pinfunction "VCC_28") (pintype "power_in"))
      (node (ref "DD4") (pin "1") (pinfunction "DIR_1") (pintype "input"))
      (node (ref "DD4") (pin "20") (pinfunction "VCC_20") (pintype "power_in"))
      (node (ref "DD5") (pin "1") (pinfunction "DIR_1") (pintype "input"))
      (node (ref "DD5") (pin "20") (pinfunction "VCC_20") (pintype "power_in"))
      (node (ref "DD5") (pin "8") (pinfunction "A6_8") (pintype "bidirectional"))
      (node (ref "DD5") (pin "9") (pinfunction "A7_9") (pintype "bidirectional"))
      (node (ref "DD6") (pin "28") (pinfunction "VCC_28") (pintype "power_in"))
      (node (ref "DD7") (pin "10") (pinfunction "VCC_10") (pintype "passive"))
      (node (ref "DD7") (pin "30") (pinfunction "AVCC_30") (pintype "passive"))
      (node (ref "DD8") (pin "31") (pinfunction "~{WE}_31") (pintype "input"))
      (node (ref "DD8") (pin "32") (pinfunction "VCC_32") (pintype "power_in"))
      (node (ref "R19") (pin "1") (pinfunction "1_1") (pintype "passive"))
      (node (ref "R20") (pin "1") (pinfunction "1_1") (pintype "passive"))
      (node (ref "R21") (pin "1") (pinfunction "1_1") (pintype "passive"))
      (node (ref "R22") (pin "1") (pinfunction "1_1") (pintype "passive"))
      (node (ref "R23") (pin "1") (pinfunction "1_1") (pintype "passive"))
      (node (ref "R24") (pin "1") (pinfunction "1_1") (pintype "passive"))
      (node (ref "R3") (pin "1") (pinfunction "1_1") (pintype "passive"))
      (node (ref "SW1") (pin "2") (pinfunction "COMMON_2") (pintype "passive"))
      (node (ref "X2") (pin "4") (pinfunction "CON_4") (pintype "passive"))
      (node (ref "X6") (pin "4") (pinfunction "CON_4") (pintype "passive"))
      (node (ref "X7") (pin "2") (pinfunction "CON_2") (pintype "passive"))
      (node (ref "Y1") (pin "14") (pinfunction "VCC_14") (pintype "power_in"))
    )
    (net (code "104") (name "unconnected-(DD1-~{BUSAK}-Pad23)") (class "Default")
      (node (ref "DD1") (pin "23") (pinfunction "~{BUSAK}_23") (pintype "output"))
    )
    (net (code "105") (name "unconnected-(DD1-~{HALT}-Pad18)") (class "Default")
      (node (ref "DD1") (pin "18") (pinfunction "~{HALT}_18") (pintype "output"))
    )
    (net (code "106") (name "unconnected-(DD1-~{REFSH}-Pad28)") (class "Default")
      (node (ref "DD1") (pin "28") (pinfunction "~{REFSH}_28") (pintype "output"))
    )
    (net (code "107") (name "unconnected-(DD2-I{slash}O-Pad31)") (class "Default")
      (node (ref "DD2") (pin "31") (pinfunction "I/O_31") (pintype "bidirectional"))
    )
    (net (code "108") (name "unconnected-(DD2-I{slash}O-Pad37)") (class "Default")
      (node (ref "DD2") (pin "37") (pinfunction "I/O_37") (pintype "bidirectional"))
    )
    (net (code "109") (name "unconnected-(DD2-I{slash}~{OE1}-Pad84)") (class "Default")
      (node (ref "DD2") (pin "84") (pinfunction "I/~{OE1}_84") (pintype "input"))
    )
    (net (code "110") (name "unconnected-(DD2-I{slash}~{OE2}{slash}GCLK2-Pad2)") (class "Default")
      (node (ref "DD2") (pin "2") (pinfunction "I/~{OE2}/GCLK2_2") (pintype "input"))
    )
    (net (code "111") (name "unconnected-(DD5-B6-Pad12)") (class "Default")
      (node (ref "DD5") (pin "12") (pinfunction "B6_12") (pintype "bidirectional"))
    )
    (net (code "112") (name "unconnected-(DD5-B7-Pad11)") (class "Default")
      (node (ref "DD5") (pin "11") (pinfunction "B7_11") (pintype "bidirectional"))
    )
    (net (code "113") (name "unconnected-(DD7-AREF-Pad32)") (class "Default")
      (node (ref "DD7") (pin "32") (pinfunction "AREF_32") (pintype "passive"))
    )
    (net (code "114") (name "unconnected-(DD7-XTAL2-Pad12)") (class "Default")
      (node (ref "DD7") (pin "12") (pinfunction "XTAL2_12") (pintype "passive"))
    )
    (net (code "115") (name "unconnected-(SW1-NO-Pad3)") (class "Default")
      (node (ref "SW1") (pin "3") (pinfunction "NO_3") (pintype "passive"))
    )
    (net (code "116") (name "unconnected-(X1B-CON-Pad2)") (class "Default")
      (node (ref "X1") (pin "2") (pinfunction "CON_2") (pintype "passive"))
    )
    (net (code "117") (name "unconnected-(X2B-CON-Pad2)") (class "Default")
      (node (ref "X2") (pin "2") (pinfunction "CON_2") (pintype "passive"))
    )
    (net (code "118") (name "unconnected-(X2F-CON-Pad6)") (class "Default")
      (node (ref "X2") (pin "6") (pinfunction "CON_6") (pintype "passive"))
    )
    (net (code "119") (name "unconnected-(X4H-CON-Pad8)") (class "Default")
      (node (ref "X4") (pin "8") (pinfunction "CON_8") (pintype "passive"))
    )
    (net (code "120") (name "unconnected-(X4I-CON-Pad9)") (class "Default")
      (node (ref "X4") (pin "9") (pinfunction "CON_9") (pintype "passive"))
    )
    (net (code "121") (name "unconnected-(X6F-CON-Pad6)") (class "Default")
      (node (ref "X6") (pin "6") (pinfunction "CON_6") (pintype "passive"))
    )
    (net (code "122") (name "unconnected-(X6G-CON-Pad7)") (class "Default")
      (node (ref "X6") (pin "7") (pinfunction "CON_7") (pintype "passive"))
    )
    (net (code "123") (name "unconnected-(X6H-CON-Pad8)") (class "Default")
      (node (ref "X6") (pin "8") (pinfunction "CON_8") (pintype "passive"))
    )
    (net (code "124") (name "unconnected-(X7C-CON-Pad3)") (class "Default")
      (node (ref "X7") (pin "3") (pinfunction "CON_3") (pintype "passive"))
    )
    (net (code "125") (name "unconnected-(X7D-CON-Pad4)") (class "Default")
      (node (ref "X7") (pin "4") (pinfunction "CON_4") (pintype "passive"))
    )
    (net (code "126") (name "unconnected-(X7F-CON-Pad6)") (class "Default")
      (node (ref "X7") (pin "6") (pinfunction "CON_6") (pintype "passive"))
    )
    (net (code "127") (name "unconnected-(X7H-CON-Pad8)") (class "Default")
      (node (ref "X7") (pin "8") (pinfunction "CON_8") (pintype "passive"))
    )
  )
)
